# 01_POWER.net
KiCad netlist of a schematic drawn in Altium Designer
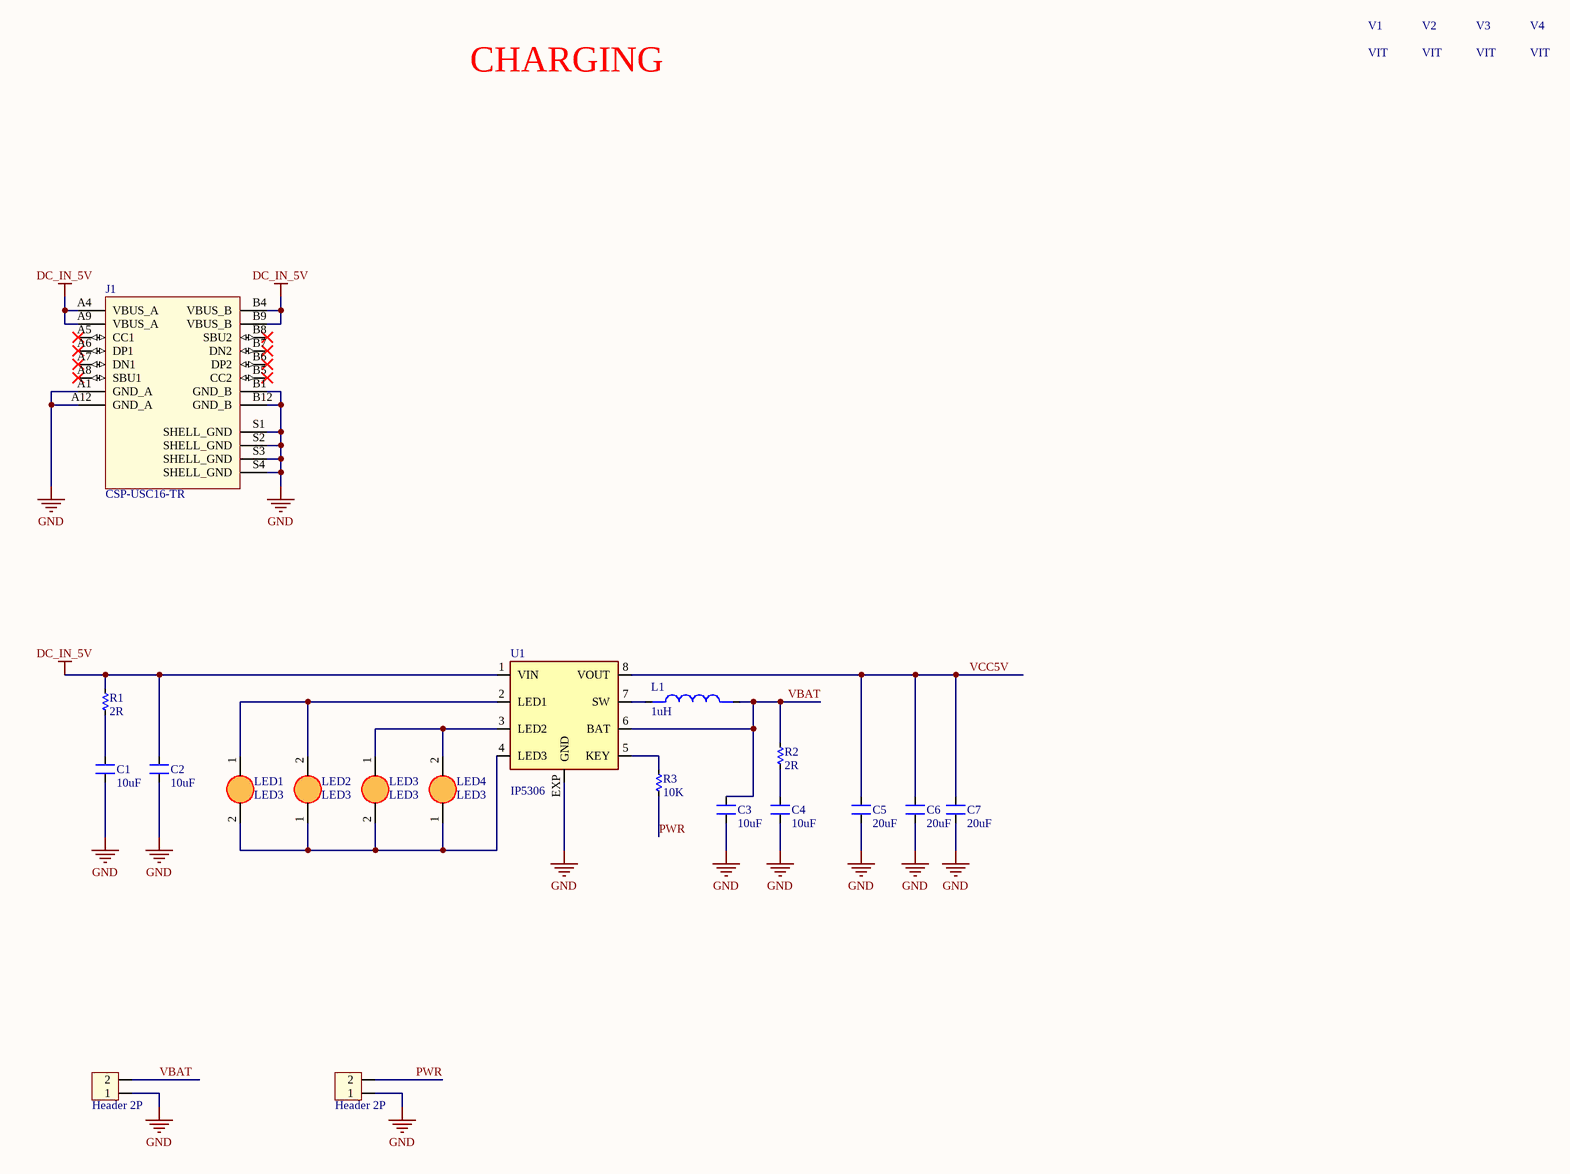
[diagram p0: 01 POWER.SchDoc]

(export (version "E")
  (design (tool "Eeschema 10.0.6"))
  (components
    (comp (ref "C1")
      (value "10uF")
      (footprint "HuanHaui_FEETEAM:C 0603")
      (description "16V")
      (libsource (lib "HuanHaui_FEETEAM") (part "CAP_SMD"))
    )
    (comp (ref "C2")
      (value "10uF")
      (footprint "HuanHaui_FEETEAM:C 0603")
      (description "16V")
      (libsource (lib "HuanHaui_FEETEAM") (part "CAP_SMD"))
    )
    (comp (ref "C3")
      (value "10uF")
      (footprint "HuanHaui_FEETEAM:C 0603")
      (description "16V")
      (libsource (lib "HuanHaui_FEETEAM") (part "CAP_SMD"))
    )
    (comp (ref "C4")
      (value "10uF")
      (footprint "HuanHaui_FEETEAM:C 0603")
      (description "16V")
      (libsource (lib "HuanHaui_FEETEAM") (part "CAP_SMD"))
    )
    (comp (ref "C5")
      (value "20uF")
      (footprint "HuanHaui_FEETEAM:C 0603")
      (description "16V")
      (libsource (lib "HuanHaui_FEETEAM") (part "CAP_SMD"))
    )
    (comp (ref "C6")
      (value "20uF")
      (footprint "HuanHaui_FEETEAM:C 0603")
      (description "16V")
      (libsource (lib "HuanHaui_FEETEAM") (part "CAP_SMD"))
    )
    (comp (ref "C7")
      (value "20uF")
      (footprint "HuanHaui_FEETEAM:C 0603")
      (description "16V")
      (libsource (lib "HuanHaui_FEETEAM") (part "CAP_SMD"))
    )
    (comp (ref "H1")
      (value "Header 2P")
      (footprint "Header 2P DC 2.54")
      (description "Cắm")
      (libsource (lib "Header") (part "Header 2P 2.54 Duc Cong"))
    )
    (comp (ref "H2")
      (value "Header 2P")
      (footprint "Header 2P DC 2.54")
      (description "Cắm")
      (libsource (lib "Header") (part "Header 2P 2.54 Duc Cong"))
    )
    (comp (ref "J1")
      (value "CSP-USC16-TR")
      (footprint "HuanHaui_FEETEAM:VALCON_CSP-USC16-TR")
      (description "CSP-USC16-TR Valcon USB Type C Surface Mount PCB Socket")
      (fields (field (name "MF") "Valcon"))
      (libsource (lib "HuanHaui_FEETEAM") (part "CSP-USC16-TR"))
    )
    (comp (ref "L1")
      (value "1uH")
      (footprint "CUON CAM SMD 0530")
      (description "SMD 0530")
      (fields (field (name "MP") "FDV0530-H-1R5M=P3"))
      (libsource (lib "Cuon Cam") (part "Cuon Cam SMD 0530"))
    )
    (comp (ref "LED1")
      (value "LED3")
      (footprint "LED3mm")
      (description "LED 3mm")
      (libsource (lib "My Library") (part "LED 3mm"))
    )
    (comp (ref "LED2")
      (value "LED3")
      (footprint "LED3mm")
      (description "LED 3mm")
      (libsource (lib "My Library") (part "LED 3mm"))
    )
    (comp (ref "LED3")
      (value "LED3")
      (footprint "LED3mm")
      (description "LED 3mm")
      (libsource (lib "My Library") (part "LED 3mm"))
    )
    (comp (ref "LED4")
      (value "LED3")
      (footprint "LED3mm")
      (description "LED 3mm")
      (libsource (lib "My Library") (part "LED 3mm"))
    )
    (comp (ref "R1")
      (value "2R")
      (footprint "HuanHaui_FEETEAM:RES-SMD-0603")
      (description "RES_SMD")
      (fields
        (field (name "MANUFACTURER") "Generic Components")
        (field (name "PUBLISHER") "Altium Hobart Technology Centre")
      )
      (libsource (lib "HuanHaui_FEETEAM") (part "Res-SMD"))
    )
    (comp (ref "R2")
      (value "2R")
      (footprint "HuanHaui_FEETEAM:RES-SMD-0603")
      (description "RES_SMD")
      (fields
        (field (name "MANUFACTURER") "Generic Components")
        (field (name "PUBLISHER") "Altium Hobart Technology Centre")
      )
      (libsource (lib "HuanHaui_FEETEAM") (part "Res-SMD"))
    )
    (comp (ref "R3")
      (value "10K")
      (footprint "HuanHaui_FEETEAM:RES-SMD-0603")
      (description "RES_SMD")
      (fields
        (field (name "MANUFACTURER") "Generic Components")
        (field (name "PUBLISHER") "Altium Hobart Technology Centre")
      )
      (libsource (lib "HuanHaui_FEETEAM") (part "Res-SMD"))
    )
    (comp (ref "U1")
      (value "IP5306")
      (footprint "SOP8-P")
      (description "RC (Pi) EMI Filter 2nd Order Low Pass 2 Channel R = 2.2kOhms, C = 1700pF 8-UFBGA, WLCSP")
      (fields (field (name "MF") "NXP USA Inc."))
      (libsource (lib "MinhNguyenCao") (part "IP5306"))
    )
    (comp (ref "V1")
      (value "VIT")
      (footprint "HuanHaui_FEETEAM:VIT_01")
      (description "VIT_3.0mm")
      (libsource (lib "HuanHaui_FEETEAM") (part "VIT"))
    )
    (comp (ref "V2")
      (value "VIT")
      (footprint "HuanHaui_FEETEAM:VIT_01")
      (description "VIT_3.0mm")
      (libsource (lib "HuanHaui_FEETEAM") (part "VIT"))
    )
    (comp (ref "V3")
      (value "VIT")
      (footprint "HuanHaui_FEETEAM:VIT_01")
      (description "VIT_3.0mm")
      (libsource (lib "HuanHaui_FEETEAM") (part "VIT"))
    )
    (comp (ref "V4")
      (value "VIT")
      (footprint "HuanHaui_FEETEAM:VIT_01")
      (description "VIT_3.0mm")
      (libsource (lib "HuanHaui_FEETEAM") (part "VIT"))
    )
  )
  (nets
    (net (code "1") (name "/PWR") (class "Default")
      (node (ref "H2") (pin "2") (pinfunction "2_2") (pintype "passive"))
      (node (ref "R3") (pin "2") (pinfunction "2_2") (pintype "passive"))
    )
    (net (code "2") (name "/VBAT") (class "Default")
      (node (ref "C3") (pin "2") (pinfunction "2_2") (pintype "passive"))
      (node (ref "H1") (pin "2") (pinfunction "2_2") (pintype "passive"))
      (node (ref "L1") (pin "2") (pinfunction "2_2") (pintype "passive"))
      (node (ref "R2") (pin "1") (pinfunction "1_1") (pintype "passive"))
      (node (ref "U1") (pin "6") (pinfunction "BAT_6") (pintype "bidirectional"))
    )
    (net (code "3") (name "/VCC5V") (class "Default")
      (node (ref "C5") (pin "2") (pinfunction "2_2") (pintype "passive"))
      (node (ref "C6") (pin "2") (pinfunction "2_2") (pintype "passive"))
      (node (ref "C7") (pin "2") (pinfunction "2_2") (pintype "passive"))
      (node (ref "U1") (pin "8") (pinfunction "VOUT_8") (pintype "bidirectional"))
    )
    (net (code "4") (name "DC_IN_5V") (class "Default")
      (node (ref "C2") (pin "2") (pinfunction "2_2") (pintype "passive"))
      (node (ref "J1") (pin "A4") (pinfunction "VBUS_A_A4") (pintype "power_in"))
      (node (ref "J1") (pin "A9") (pinfunction "VBUS_A_A9") (pintype "power_in"))
      (node (ref "J1") (pin "B4") (pinfunction "VBUS_B_B4") (pintype "power_in"))
      (node (ref "J1") (pin "B9") (pinfunction "VBUS_B_B9") (pintype "power_in"))
      (node (ref "R1") (pin "1") (pinfunction "1_1") (pintype "passive"))
      (node (ref "U1") (pin "1") (pinfunction "VIN_1") (pintype "bidirectional"))
    )
    (net (code "5") (name "GND") (class "Default")
      (node (ref "C1") (pin "1") (pinfunction "1_1") (pintype "passive"))
      (node (ref "C2") (pin "1") (pinfunction "1_1") (pintype "passive"))
      (node (ref "C3") (pin "1") (pinfunction "1_1") (pintype "passive"))
      (node (ref "C4") (pin "1") (pinfunction "1_1") (pintype "passive"))
      (node (ref "C5") (pin "1") (pinfunction "1_1") (pintype "passive"))
      (node (ref "C6") (pin "1") (pinfunction "1_1") (pintype "passive"))
      (node (ref "C7") (pin "1") (pinfunction "1_1") (pintype "passive"))
      (node (ref "H1") (pin "1") (pinfunction "1_1") (pintype "passive"))
      (node (ref "H2") (pin "1") (pinfunction "1_1") (pintype "passive"))
      (node (ref "J1") (pin "A1") (pinfunction "GND_A_A1") (pintype "power_in"))
      (node (ref "J1") (pin "A12") (pinfunction "GND_A_A12") (pintype "power_in"))
      (node (ref "J1") (pin "B1") (pinfunction "GND_B_B1") (pintype "power_in"))
      (node (ref "J1") (pin "B12") (pinfunction "GND_B_B12") (pintype "power_in"))
      (node (ref "J1") (pin "S1") (pinfunction "SHELL_GND_S1") (pintype "power_in"))
      (node (ref "J1") (pin "S2") (pinfunction "SHELL_GND_S2") (pintype "power_in"))
      (node (ref "J1") (pin "S3") (pinfunction "SHELL_GND_S3") (pintype "power_in"))
      (node (ref "J1") (pin "S4") (pinfunction "SHELL_GND_S4") (pintype "power_in"))
      (node (ref "U1") (pin "EXP") (pinfunction "GND_EXP") (pintype "bidirectional"))
    )
    (net (code "6") (name "Net-(C1-Pad2)") (class "Default")
      (node (ref "C1") (pin "2") (pinfunction "2_2") (pintype "passive"))
      (node (ref "R1") (pin "2") (pinfunction "2_2") (pintype "passive"))
    )
    (net (code "7") (name "Net-(C4-Pad2)") (class "Default")
      (node (ref "C4") (pin "2") (pinfunction "2_2") (pintype "passive"))
      (node (ref "R2") (pin "2") (pinfunction "2_2") (pintype "passive"))
    )
    (net (code "8") (name "Net-(LED1-A)") (class "Default")
      (node (ref "LED1") (pin "1") (pinfunction "A_1") (pintype "passive"))
      (node (ref "LED2") (pin "2") (pinfunction "K_2") (pintype "passive"))
      (node (ref "U1") (pin "2") (pinfunction "LED1_2") (pintype "bidirectional"))
    )
    (net (code "9") (name "Net-(LED1-K)") (class "Default")
      (node (ref "LED1") (pin "2") (pinfunction "K_2") (pintype "passive"))
      (node (ref "LED2") (pin "1") (pinfunction "A_1") (pintype "passive"))
      (node (ref "LED3") (pin "2") (pinfunction "K_2") (pintype "passive"))
      (node (ref "LED4") (pin "1") (pinfunction "A_1") (pintype "passive"))
      (node (ref "U1") (pin "4") (pinfunction "LED3_4") (pintype "bidirectional"))
    )
    (net (code "10") (name "Net-(LED3-A)") (class "Default")
      (node (ref "LED3") (pin "1") (pinfunction "A_1") (pintype "passive"))
      (node (ref "LED4") (pin "2") (pinfunction "K_2") (pintype "passive"))
      (node (ref "U1") (pin "3") (pinfunction "LED2_3") (pintype "bidirectional"))
    )
    (net (code "11") (name "Net-(U1-KEY)") (class "Default")
      (node (ref "R3") (pin "1") (pinfunction "1_1") (pintype "passive"))
      (node (ref "U1") (pin "5") (pinfunction "KEY_5") (pintype "bidirectional"))
    )
    (net (code "12") (name "Net-(U1-SW)") (class "Default")
      (node (ref "L1") (pin "1") (pinfunction "1_1") (pintype "passive"))
      (node (ref "U1") (pin "7") (pinfunction "SW_7") (pintype "bidirectional"))
    )
    (net (code "13") (name "unconnected-(J1-CC1-PadA5)") (class "Default")
      (node (ref "J1") (pin "A5") (pinfunction "CC1_A5") (pintype "bidirectional+no_connect"))
    )
    (net (code "14") (name "unconnected-(J1-CC2-PadB5)") (class "Default")
      (node (ref "J1") (pin "B5") (pinfunction "CC2_B5") (pintype "bidirectional+no_connect"))
    )
    (net (code "15") (name "unconnected-(J1-DN1-PadA7)") (class "Default")
      (node (ref "J1") (pin "A7") (pinfunction "DN1_A7") (pintype "bidirectional+no_connect"))
    )
    (net (code "16") (name "unconnected-(J1-DN2-PadB7)") (class "Default")
      (node (ref "J1") (pin "B7") (pinfunction "DN2_B7") (pintype "bidirectional+no_connect"))
    )
    (net (code "17") (name "unconnected-(J1-DP1-PadA6)") (class "Default")
      (node (ref "J1") (pin "A6") (pinfunction "DP1_A6") (pintype "bidirectional+no_connect"))
    )
    (net (code "18") (name "unconnected-(J1-DP2-PadB6)") (class "Default")
      (node (ref "J1") (pin "B6") (pinfunction "DP2_B6") (pintype "bidirectional+no_connect"))
    )
    (net (code "19") (name "unconnected-(J1-SBU1-PadA8)") (class "Default")
      (node (ref "J1") (pin "A8") (pinfunction "SBU1_A8") (pintype "bidirectional+no_connect"))
    )
    (net (code "20") (name "unconnected-(J1-SBU2-PadB8)") (class "Default")
      (node (ref "J1") (pin "B8") (pinfunction "SBU2_B8") (pintype "bidirectional+no_connect"))
    )
  )
)
